# beacon.net
KiCad netlist of a schematic drawn in EAGLE
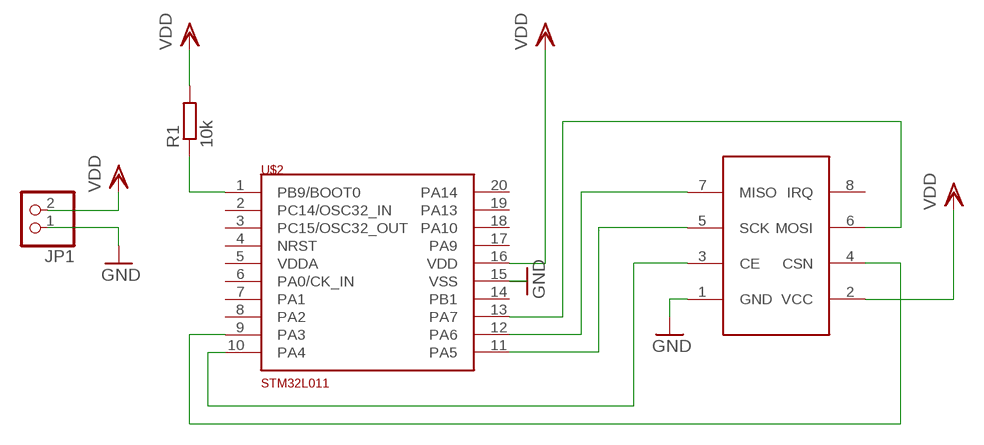
[diagram p0: schematic, sheet 1]

(export (version "E")
  (design (tool "Eeschema 10.0.6"))
  (components
    (comp (ref "JP1")
      (value "PINHD-1X2")
      (footprint "eagle-import:1X02")
      (libsource (lib "eagle-import") (part "PINHD-1X2"))
    )
    (comp (ref "R1")
      (value "10k")
      (footprint "eagle-import:R0805")
      (libsource (lib "eagle-import") (part "R-EU_R0805"))
    )
    (comp (ref "U$1")
      (value "RF24013")
      (footprint "eagle-import:PIN")
      (libsource (lib "eagle-import") (part "RF24013"))
    )
    (comp (ref "U$2")
      (value "STM32L011")
      (footprint "eagle-import:SSOP20")
      (libsource (lib "eagle-import") (part "STM32L011"))
    )
  )
  (nets
    (net (code "1") (name "/VDDA") (class "Default")
      (node (ref "U$2") (pin "5") (pinfunction "VDDA_5") (pintype "power_in"))
    )
    (net (code "2") (name "GND") (class "Default")
      (node (ref "JP1") (pin "1") (pinfunction "1_1") (pintype "passive"))
      (node (ref "U$1") (pin "1") (pinfunction "GND_1") (pintype "power_in"))
      (node (ref "U$2") (pin "15") (pinfunction "VSS_15") (pintype "power_in"))
    )
    (net (code "3") (name "Net-(U$1-CE)") (class "Default")
      (node (ref "U$1") (pin "3") (pinfunction "CE_3") (pintype "input"))
      (node (ref "U$2") (pin "10") (pinfunction "PA4_10") (pintype "bidirectional"))
    )
    (net (code "4") (name "Net-(U$1-CSN)") (class "Default")
      (node (ref "U$1") (pin "4") (pinfunction "CSN_4") (pintype "input"))
      (node (ref "U$2") (pin "9") (pinfunction "PA3_9") (pintype "bidirectional"))
    )
    (net (code "5") (name "Net-(U$1-MISO)") (class "Default")
      (node (ref "U$1") (pin "7") (pinfunction "MISO_7") (pintype "bidirectional"))
      (node (ref "U$2") (pin "12") (pinfunction "PA6_12") (pintype "bidirectional"))
    )
    (net (code "6") (name "Net-(U$1-MOSI)") (class "Default")
      (node (ref "U$1") (pin "6") (pinfunction "MOSI_6") (pintype "input"))
      (node (ref "U$2") (pin "13") (pinfunction "PA7_13") (pintype "bidirectional"))
    )
    (net (code "7") (name "Net-(U$1-SCK)") (class "Default")
      (node (ref "U$1") (pin "5") (pinfunction "SCK_5") (pintype "input"))
      (node (ref "U$2") (pin "11") (pinfunction "PA5_11") (pintype "bidirectional"))
    )
    (net (code "8") (name "Net-(U$2-PB9{slash}BOOT0)") (class "Default")
      (node (ref "R1") (pin "1") (pinfunction "1_1") (pintype "passive"))
      (node (ref "U$2") (pin "1") (pinfunction "PB9/BOOT0_1") (pintype "bidirectional"))
    )
    (net (code "9") (name "VDD") (class "Default")
      (node (ref "JP1") (pin "2") (pinfunction "2_2") (pintype "passive"))
      (node (ref "R1") (pin "2") (pinfunction "2_2") (pintype "passive"))
      (node (ref "U$1") (pin "2") (pinfunction "VCC_2") (pintype "power_in"))
      (node (ref "U$2") (pin "16") (pinfunction "VDD_16") (pintype "power_in"))
    )
    (net (code "10") (name "unconnected-(U$1-IRQ-Pad8)") (class "Default")
      (node (ref "U$1") (pin "8") (pinfunction "IRQ_8") (pintype "bidirectional"))
    )
    (net (code "11") (name "unconnected-(U$2-NRST-Pad4)") (class "Default")
      (node (ref "U$2") (pin "4") (pinfunction "NRST_4") (pintype "bidirectional"))
    )
    (net (code "12") (name "unconnected-(U$2-PA0{slash}CK_IN-Pad6)") (class "Default")
      (node (ref "U$2") (pin "6") (pinfunction "PA0/CK_IN_6") (pintype "bidirectional"))
    )
    (net (code "13") (name "unconnected-(U$2-PA1-Pad7)") (class "Default")
      (node (ref "U$2") (pin "7") (pinfunction "PA1_7") (pintype "bidirectional"))
    )
    (net (code "14") (name "unconnected-(U$2-PA2-Pad8)") (class "Default")
      (node (ref "U$2") (pin "8") (pinfunction "PA2_8") (pintype "bidirectional"))
    )
    (net (code "15") (name "unconnected-(U$2-PA9-Pad17)") (class "Default")
      (node (ref "U$2") (pin "17") (pinfunction "PA9_17") (pintype "bidirectional"))
    )
    (net (code "16") (name "unconnected-(U$2-PA10-Pad18)") (class "Default")
      (node (ref "U$2") (pin "18") (pinfunction "PA10_18") (pintype "bidirectional"))
    )
    (net (code "17") (name "unconnected-(U$2-PA13-Pad19)") (class "Default")
      (node (ref "U$2") (pin "19") (pinfunction "PA13_19") (pintype "bidirectional"))
    )
    (net (code "18") (name "unconnected-(U$2-PA14-Pad20)") (class "Default")
      (node (ref "U$2") (pin "20") (pinfunction "PA14_20") (pintype "bidirectional"))
    )
    (net (code "19") (name "unconnected-(U$2-PB1-Pad14)") (class "Default")
      (node (ref "U$2") (pin "14") (pinfunction "PB1_14") (pintype "bidirectional"))
    )
    (net (code "20") (name "unconnected-(U$2-PC14{slash}OSC32_IN-Pad2)") (class "Default")
      (node (ref "U$2") (pin "2") (pinfunction "PC14/OSC32_IN_2") (pintype "bidirectional"))
    )
    (net (code "21") (name "unconnected-(U$2-PC15{slash}OSC32_OUT-Pad3)") (class "Default")
      (node (ref "U$2") (pin "3") (pinfunction "PC15/OSC32_OUT_3") (pintype "bidirectional"))
    )
  )
)
